# Power_Supply.net
KiCad netlist of a schematic drawn in Altium Designer
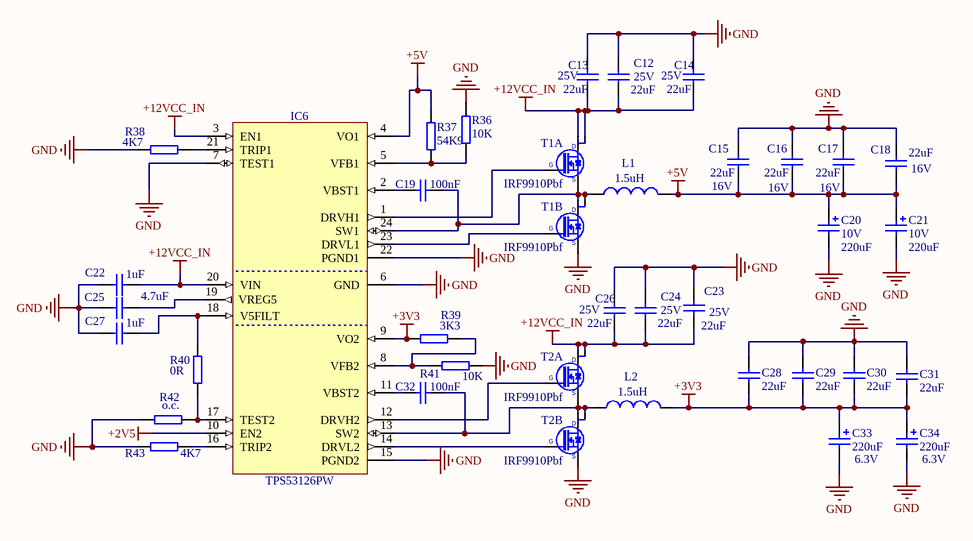
[diagram p0: Power_Supply.SchDoc]

(export (version "E")
  (design (tool "Eeschema 10.0.6"))
  (components
    (comp (ref "C12")
      (value "22uF")
      (footprint "CC3216-1206")
      (description "Capacitor")
      (fields
        (field (name "TOLERANCE") "±10%")
        (field (name "VOLTAGE") "25V")
        (field (name "Comment") "22uF 25V")
        (field (name "PUBLISHER") "Altium Limited")
      )
      (libsource (lib "wr_switch") (part "Cap"))
    )
    (comp (ref "C13")
      (value "22uF")
      (footprint "CC3216-1206")
      (description "Capacitor")
      (fields
        (field (name "TOLERANCE") "±10%")
        (field (name "VOLTAGE") "25V")
        (field (name "Comment") "22uF 25V")
        (field (name "PUBLISHER") "Altium Limited")
      )
      (libsource (lib "wr_switch") (part "Cap"))
    )
    (comp (ref "C14")
      (value "22uF")
      (footprint "CC3216-1206")
      (description "Capacitor")
      (fields
        (field (name "TOLERANCE") "±10%")
        (field (name "VOLTAGE") "25V")
        (field (name "Comment") "22uF 25V")
        (field (name "PUBLISHER") "Altium Limited")
      )
      (libsource (lib "wr_switch") (part "Cap"))
    )
    (comp (ref "C15")
      (value "22uF")
      (footprint "CC2012-0805")
      (description "Capacitor")
      (fields
        (field (name "TOLERANCE") "±10%")
        (field (name "VOLTAGE") "16V")
        (field (name "Comment") "22uF 16V")
        (field (name "PUBLISHER") "Altium Limited")
      )
      (libsource (lib "wr_switch") (part "Cap"))
    )
    (comp (ref "C16")
      (value "22uF")
      (footprint "CC2012-0805")
      (description "Capacitor")
      (fields
        (field (name "TOLERANCE") "±10%")
        (field (name "VOLTAGE") "16V")
        (field (name "Comment") "22uF 16V")
        (field (name "PUBLISHER") "Altium Limited")
      )
      (libsource (lib "wr_switch") (part "Cap"))
    )
    (comp (ref "C17")
      (value "22uF")
      (footprint "CC2012-0805")
      (description "Capacitor")
      (fields
        (field (name "TOLERANCE") "±10%")
        (field (name "VOLTAGE") "16V")
        (field (name "Comment") "22uF 16V")
        (field (name "PUBLISHER") "Altium Limited")
      )
      (libsource (lib "wr_switch") (part "Cap"))
    )
    (comp (ref "C18")
      (value "22uF")
      (footprint "CC2012-0805")
      (description "Capacitor")
      (fields
        (field (name "TOLERANCE") "±10%")
        (field (name "VOLTAGE") "16V")
        (field (name "Comment") "22uF 16V")
        (field (name "PUBLISHER") "Altium Limited")
      )
      (libsource (lib "wr_switch") (part "Cap"))
    )
    (comp (ref "C19")
      (value "100nF")
      (footprint "CC1608-0603")
      (description "Capacitor")
      (fields
        (field (name "TOLERANCE") "±10%")
        (field (name "VOLTAGE") "16V")
        (field (name "PUBLISHER") "Altium Limited")
      )
      (libsource (lib "wr_switch") (part "Cap"))
    )
    (comp (ref "C20")
      (value "220uF")
      (footprint "D")
      (description "Polarized Capacitor Tantalum")
      (fields
        (field (name "TOLERANCE") "±20%")
        (field (name "VOLTAGE") "10V")
        (field (name "Comment") "220uF 10V")
        (field (name "PUBLISHER") "Altium Limited")
      )
      (libsource (lib "wr_switch") (part "Cap Pol1"))
    )
    (comp (ref "C21")
      (value "220uF")
      (footprint "D")
      (description "Polarized Capacitor Tantalum")
      (fields
        (field (name "TOLERANCE") "±20%")
        (field (name "VOLTAGE") "10V")
        (field (name "Comment") "220uF 10V")
        (field (name "PUBLISHER") "Altium Limited")
      )
      (libsource (lib "wr_switch") (part "Cap Pol1"))
    )
    (comp (ref "C22")
      (value "1uF")
      (footprint "CC1608-0603")
      (description "Capacitor")
      (fields
        (field (name "TOLERANCE") "±10%")
        (field (name "VOLTAGE") "25V")
        (field (name "PUBLISHER") "Altium Limited")
      )
      (libsource (lib "wr_switch") (part "Cap"))
    )
    (comp (ref "C23")
      (value "22uF")
      (footprint "CC3216-1206")
      (description "Capacitor")
      (fields
        (field (name "TOLERANCE") "±10%")
        (field (name "VOLTAGE") "25V")
        (field (name "Comment") "22uF 25V")
        (field (name "PUBLISHER") "Altium Limited")
      )
      (libsource (lib "wr_switch") (part "Cap"))
    )
    (comp (ref "C24")
      (value "22uF")
      (footprint "CC3216-1206")
      (description "Capacitor")
      (fields
        (field (name "TOLERANCE") "±10%")
        (field (name "VOLTAGE") "25V")
        (field (name "Comment") "22uF 25V")
        (field (name "PUBLISHER") "Altium Limited")
      )
      (libsource (lib "wr_switch") (part "Cap"))
    )
    (comp (ref "C25")
      (value "4.7uF")
      (footprint "CC1608-0603")
      (description "Capacitor")
      (fields
        (field (name "TOLERANCE") "±10%")
        (field (name "VOLTAGE") "10V")
        (field (name "PUBLISHER") "Altium Limited")
      )
      (libsource (lib "wr_switch") (part "Cap"))
    )
    (comp (ref "C26")
      (value "22uF")
      (footprint "CC3216-1206")
      (description "Capacitor")
      (fields
        (field (name "TOLERANCE") "±10%")
        (field (name "VOLTAGE") "25V")
        (field (name "Comment") "22uF 25V")
        (field (name "PUBLISHER") "Altium Limited")
      )
      (libsource (lib "wr_switch") (part "Cap"))
    )
    (comp (ref "C27")
      (value "1uF")
      (footprint "CC1608-0603")
      (description "Capacitor")
      (fields
        (field (name "TOLERANCE") "±10%")
        (field (name "VOLTAGE") "25V")
        (field (name "PUBLISHER") "Altium Limited")
      )
      (libsource (lib "wr_switch") (part "Cap"))
    )
    (comp (ref "C28")
      (value "22uF")
      (footprint "CC2012-0805")
      (description "Capacitor")
      (fields
        (field (name "TOLERANCE") "±20%")
        (field (name "VOLTAGE") "6.3V")
        (field (name "PUBLISHER") "Altium Limited")
      )
      (libsource (lib "wr_switch") (part "Cap"))
    )
    (comp (ref "C29")
      (value "22uF")
      (footprint "CC2012-0805")
      (description "Capacitor")
      (fields
        (field (name "TOLERANCE") "±20%")
        (field (name "VOLTAGE") "6.3V")
        (field (name "PUBLISHER") "Altium Limited")
      )
      (libsource (lib "wr_switch") (part "Cap"))
    )
    (comp (ref "C30")
      (value "22uF")
      (footprint "CC2012-0805")
      (description "Capacitor")
      (fields
        (field (name "TOLERANCE") "±20%")
        (field (name "VOLTAGE") "6.3V")
        (field (name "PUBLISHER") "Altium Limited")
      )
      (libsource (lib "wr_switch") (part "Cap"))
    )
    (comp (ref "C31")
      (value "22uF")
      (footprint "CC2012-0805")
      (description "Capacitor")
      (fields
        (field (name "TOLERANCE") "±20%")
        (field (name "VOLTAGE") "6.3V")
        (field (name "PUBLISHER") "Altium Limited")
      )
      (libsource (lib "wr_switch") (part "Cap"))
    )
    (comp (ref "C32")
      (value "100nF")
      (footprint "CC1608-0603")
      (description "Capacitor")
      (fields
        (field (name "TOLERANCE") "±10%")
        (field (name "VOLTAGE") "16V")
        (field (name "PUBLISHER") "Altium Limited")
      )
      (libsource (lib "wr_switch") (part "Cap"))
    )
    (comp (ref "C33")
      (value "220uF")
      (footprint "D")
      (description "Polarized Capacitor Tantalum")
      (fields
        (field (name "TOLERANCE") "±20%")
        (field (name "VOLTAGE") "6.3V")
        (field (name "PUBLISHER") "Altium Limited")
      )
      (libsource (lib "wr_switch") (part "Cap Pol1"))
    )
    (comp (ref "C34")
      (value "220uF")
      (footprint "D")
      (description "Polarized Capacitor Tantalum")
      (fields
        (field (name "TOLERANCE") "±20%")
        (field (name "VOLTAGE") "6.3V")
        (field (name "PUBLISHER") "Altium Limited")
      )
      (libsource (lib "wr_switch") (part "Cap Pol1"))
    )
    (comp (ref "IC6")
      (value "TPS53126PW")
      (footprint "SOP65P640X120-24N")
      (description "Dual Synchronous Step-Down Controller For Low Voltage Power Rails")
      (fields (field (name "MANUFACTURER") "TEXAS INSTRUMENTS") (field (name "AUTHOR") "CERN DEM JLC"))
      (libsource (lib "wr_switch") (part "TPS53126PW"))
    )
    (comp (ref "L1")
      (value "1.5uH")
      (footprint "IHLP2525")
      (description "Low Profile, High Current Inductor")
      (fields
        (field (name "MANUFACTURER") "Vishay/Dale")
        (field (name "Comment") "IHLP2525CZER1R5M01")
        (field (name "PUBLISHER") "Altium Limited")
      )
      (libsource (lib "Miscellaneous Devices") (part "Inductor"))
    )
    (comp (ref "L2")
      (value "1.5uH")
      (footprint "IHLP2525")
      (description "Low Profile, High Current Inductor")
      (fields
        (field (name "MANUFACTURER") "Vishay/Dale")
        (field (name "Comment") "IHLP2525CZER1R5M01")
        (field (name "PUBLISHER") "Altium Limited")
      )
      (libsource (lib "Miscellaneous Devices") (part "Inductor"))
    )
    (comp (ref "R36")
      (value "10K")
      (footprint "0603")
      (description "SMD Resistor")
      (fields (field (name "TOLERANCE") "±1%"))
      (libsource (lib "wr_switch") (part "RES_SMD"))
    )
    (comp (ref "R37")
      (value "54K9")
      (footprint "0603")
      (description "SMD Resistor")
      (fields (field (name "TOLERANCE") "±1%"))
      (libsource (lib "wr_switch") (part "RES_SMD"))
    )
    (comp (ref "R38")
      (value "4K7")
      (footprint "0603")
      (description "SMD Resistor")
      (fields (field (name "TOLERANCE") "±1%"))
      (libsource (lib "wr_switch") (part "RES_SMD"))
    )
    (comp (ref "R39")
      (value "3K3")
      (footprint "0603")
      (description "SMD Resistor")
      (fields (field (name "TOLERANCE") "±1%"))
      (libsource (lib "wr_switch") (part "RES_SMD"))
    )
    (comp (ref "R40")
      (value "0R")
      (footprint "0603")
      (description "SMD Resistor")
      (libsource (lib "wr_switch") (part "RES_SMD"))
    )
    (comp (ref "R41")
      (value "10K")
      (footprint "0603")
      (description "SMD Resistor")
      (fields (field (name "TOLERANCE") "±1%"))
      (libsource (lib "wr_switch") (part "RES_SMD"))
    )
    (comp (ref "R42")
      (value "o.c.")
      (footprint "0603")
      (description "SMD Resistor")
      (fields (field (name "TOLERANCE") "NA"))
      (libsource (lib "wr_switch") (part "RES_SMD"))
    )
    (comp (ref "R43")
      (value "4K7")
      (footprint "0603")
      (description "SMD Resistor")
      (fields (field (name "TOLERANCE") "±1%"))
      (libsource (lib "wr_switch") (part "RES_SMD"))
    )
    (comp (ref "T1")
      (value "IRF9910Pbf")
      (footprint "SOIC127P600X175-8N")
      (description "Dual SO-8 MOSFET For POL Cconverter")
      (fields (field (name "MANUFACTURER") "INTERNATIONAL RECTIFIER") (field (name "AUTHOR") "CERN DEM JLC"))
      (libsource (lib "ICs And Semiconductors") (part "IRF9910"))
    )
    (comp (ref "T2")
      (value "IRF9910Pbf")
      (footprint "SOIC127P600X175-8N")
      (description "Dual SO-8 MOSFET For POL Cconverter")
      (fields (field (name "MANUFACTURER") "INTERNATIONAL RECTIFIER") (field (name "AUTHOR") "CERN DEM JLC"))
      (libsource (lib "ICs And Semiconductors") (part "IRF9910"))
    )
  )
  (nets
    (net (code "1") (name "+2V5") (class "Default")
      (node (ref "IC6") (pin "10") (pinfunction "EN2_10") (pintype "input"))
    )
    (net (code "2") (name "+3V3") (class "Default")
      (node (ref "C28") (pin "2") (pinfunction "2_2") (pintype "passive"))
      (node (ref "C29") (pin "1") (pinfunction "1_1") (pintype "passive"))
      (node (ref "C30") (pin "1") (pinfunction "1_1") (pintype "passive"))
      (node (ref "C31") (pin "1") (pinfunction "1_1") (pintype "passive"))
      (node (ref "C33") (pin "1") (pinfunction "1_1") (pintype "passive"))
      (node (ref "C34") (pin "1") (pinfunction "1_1") (pintype "passive"))
      (node (ref "IC6") (pin "9") (pinfunction "VO2_9") (pintype "input"))
      (node (ref "L2") (pin "2") (pinfunction "2_2") (pintype "passive"))
      (node (ref "R39") (pin "1") (pinfunction "1_1") (pintype "passive"))
    )
    (net (code "3") (name "+5V") (class "Default")
      (node (ref "C15") (pin "1") (pinfunction "1_1") (pintype "passive"))
      (node (ref "C16") (pin "1") (pinfunction "1_1") (pintype "passive"))
      (node (ref "C17") (pin "1") (pinfunction "1_1") (pintype "passive"))
      (node (ref "C18") (pin "1") (pinfunction "1_1") (pintype "passive"))
      (node (ref "C20") (pin "1") (pinfunction "1_1") (pintype "passive"))
      (node (ref "C21") (pin "1") (pinfunction "1_1") (pintype "passive"))
      (node (ref "IC6") (pin "4") (pinfunction "VO1_4") (pintype "input"))
      (node (ref "L1") (pin "2") (pinfunction "2_2") (pintype "passive"))
      (node (ref "R37") (pin "2") (pinfunction "2_2") (pintype "passive"))
    )
    (net (code "4") (name "+12VCC_IN") (class "Default")
      (node (ref "C12") (pin "1") (pinfunction "1_1") (pintype "passive"))
      (node (ref "C13") (pin "1") (pinfunction "1_1") (pintype "passive"))
      (node (ref "C14") (pin "1") (pinfunction "1_1") (pintype "passive"))
      (node (ref "C22") (pin "2") (pinfunction "2_2") (pintype "passive"))
      (node (ref "C23") (pin "1") (pinfunction "1_1") (pintype "passive"))
      (node (ref "C24") (pin "1") (pinfunction "1_1") (pintype "passive"))
      (node (ref "C26") (pin "1") (pinfunction "1_1") (pintype "passive"))
      (node (ref "IC6") (pin "20") (pinfunction "VIN_20") (pintype "input"))
      (node (ref "IC6") (pin "3") (pinfunction "EN1_3") (pintype "input"))
      (node (ref "T1") (pin "5") (pinfunction "D_5") (pintype "passive"))
      (node (ref "T1") (pin "6") (pinfunction "D_6") (pintype "passive"))
      (node (ref "T2") (pin "5") (pinfunction "D_5") (pintype "passive"))
      (node (ref "T2") (pin "6") (pinfunction "D_6") (pintype "passive"))
    )
    (net (code "5") (name "GND") (class "Default")
      (node (ref "C12") (pin "2") (pinfunction "2_2") (pintype "passive"))
      (node (ref "C13") (pin "2") (pinfunction "2_2") (pintype "passive"))
      (node (ref "C14") (pin "2") (pinfunction "2_2") (pintype "passive"))
      (node (ref "C15") (pin "2") (pinfunction "2_2") (pintype "passive"))
      (node (ref "C16") (pin "2") (pinfunction "2_2") (pintype "passive"))
      (node (ref "C17") (pin "2") (pinfunction "2_2") (pintype "passive"))
      (node (ref "C18") (pin "2") (pinfunction "2_2") (pintype "passive"))
      (node (ref "C20") (pin "2") (pinfunction "2_2") (pintype "passive"))
      (node (ref "C21") (pin "2") (pinfunction "2_2") (pintype "passive"))
      (node (ref "C22") (pin "1") (pinfunction "1_1") (pintype "passive"))
      (node (ref "C23") (pin "2") (pinfunction "2_2") (pintype "passive"))
      (node (ref "C24") (pin "2") (pinfunction "2_2") (pintype "passive"))
      (node (ref "C25") (pin "2") (pinfunction "2_2") (pintype "passive"))
      (node (ref "C26") (pin "2") (pinfunction "2_2") (pintype "passive"))
      (node (ref "C27") (pin "1") (pinfunction "1_1") (pintype "passive"))
      (node (ref "C28") (pin "1") (pinfunction "1_1") (pintype "passive"))
      (node (ref "C29") (pin "2") (pinfunction "2_2") (pintype "passive"))
      (node (ref "C30") (pin "2") (pinfunction "2_2") (pintype "passive"))
      (node (ref "C31") (pin "2") (pinfunction "2_2") (pintype "passive"))
      (node (ref "C33") (pin "2") (pinfunction "2_2") (pintype "passive"))
      (node (ref "C34") (pin "2") (pinfunction "2_2") (pintype "passive"))
      (node (ref "IC6") (pin "15") (pinfunction "PGND2_15") (pintype "power_in"))
      (node (ref "IC6") (pin "22") (pinfunction "PGND1_22") (pintype "power_in"))
      (node (ref "IC6") (pin "6") (pinfunction "GND_6") (pintype "power_in"))
      (node (ref "IC6") (pin "7") (pinfunction "TEST1_7") (pintype "bidirectional"))
      (node (ref "R36") (pin "2") (pinfunction "2_2") (pintype "passive"))
      (node (ref "R38") (pin "2") (pinfunction "2_2") (pintype "passive"))
      (node (ref "R41") (pin "1") (pinfunction "1_1") (pintype "passive"))
      (node (ref "R42") (pin "2") (pinfunction "2_2") (pintype "passive"))
      (node (ref "R43") (pin "2") (pinfunction "2_2") (pintype "passive"))
      (node (ref "T1") (pin "1") (pinfunction "S_1") (pintype "passive"))
      (node (ref "T2") (pin "1") (pinfunction "S_1") (pintype "passive"))
    )
    (net (code "6") (name "Net-(IC6-DRVH1)") (class "Default")
      (node (ref "IC6") (pin "1") (pinfunction "DRVH1_1") (pintype "output"))
      (node (ref "T1") (pin "4") (pinfunction "G_4") (pintype "passive"))
    )
    (net (code "7") (name "Net-(IC6-DRVH2)") (class "Default")
      (node (ref "IC6") (pin "12") (pinfunction "DRVH2_12") (pintype "output"))
      (node (ref "T2") (pin "4") (pinfunction "G_4") (pintype "passive"))
    )
    (net (code "8") (name "Net-(IC6-DRVL1)") (class "Default")
      (node (ref "IC6") (pin "23") (pinfunction "DRVL1_23") (pintype "output"))
      (node (ref "T1") (pin "2") (pinfunction "G_2") (pintype "passive"))
    )
    (net (code "9") (name "Net-(IC6-DRVL2)") (class "Default")
      (node (ref "IC6") (pin "14") (pinfunction "DRVL2_14") (pintype "output"))
      (node (ref "T2") (pin "2") (pinfunction "G_2") (pintype "passive"))
    )
    (net (code "10") (name "Net-(IC6-SW1)") (class "Default")
      (node (ref "C19") (pin "1") (pinfunction "1_1") (pintype "passive"))
      (node (ref "IC6") (pin "24") (pinfunction "SW1_24") (pintype "bidirectional"))
      (node (ref "L1") (pin "1") (pinfunction "1_1") (pintype "passive"))
      (node (ref "T1") (pin "3") (pinfunction "S_3") (pintype "passive"))
      (node (ref "T1") (pin "7") (pinfunction "D_7") (pintype "passive"))
      (node (ref "T1") (pin "8") (pinfunction "D_8") (pintype "passive"))
    )
    (net (code "11") (name "Net-(IC6-SW2)") (class "Default")
      (node (ref "C32") (pin "1") (pinfunction "1_1") (pintype "passive"))
      (node (ref "IC6") (pin "13") (pinfunction "SW2_13") (pintype "bidirectional"))
      (node (ref "L2") (pin "1") (pinfunction "1_1") (pintype "passive"))
      (node (ref "T2") (pin "3") (pinfunction "S_3") (pintype "passive"))
      (node (ref "T2") (pin "7") (pinfunction "D_7") (pintype "passive"))
      (node (ref "T2") (pin "8") (pinfunction "D_8") (pintype "passive"))
    )
    (net (code "12") (name "Net-(IC6-TEST2)") (class "Default")
      (node (ref "IC6") (pin "17") (pinfunction "TEST2_17") (pintype "input"))
      (node (ref "R40") (pin "2") (pinfunction "2_2") (pintype "passive"))
      (node (ref "R42") (pin "1") (pinfunction "1_1") (pintype "passive"))
    )
    (net (code "13") (name "Net-(IC6-TRIP1)") (class "Default")
      (node (ref "IC6") (pin "21") (pinfunction "TRIP1_21") (pintype "input"))
      (node (ref "R38") (pin "1") (pinfunction "1_1") (pintype "passive"))
    )
    (net (code "14") (name "Net-(IC6-TRIP2)") (class "Default")
      (node (ref "IC6") (pin "16") (pinfunction "TRIP2_16") (pintype "input"))
      (node (ref "R43") (pin "1") (pinfunction "1_1") (pintype "passive"))
    )
    (net (code "15") (name "Net-(IC6-V5FILT)") (class "Default")
      (node (ref "C27") (pin "2") (pinfunction "2_2") (pintype "passive"))
      (node (ref "IC6") (pin "18") (pinfunction "V5FILT_18") (pintype "input"))
      (node (ref "R40") (pin "1") (pinfunction "1_1") (pintype "passive"))
    )
    (net (code "16") (name "Net-(IC6-VBST1)") (class "Default")
      (node (ref "C19") (pin "2") (pinfunction "2_2") (pintype "passive"))
      (node (ref "IC6") (pin "2") (pinfunction "VBST1_2") (pintype "input"))
    )
    (net (code "17") (name "Net-(IC6-VBST2)") (class "Default")
      (node (ref "C32") (pin "2") (pinfunction "2_2") (pintype "passive"))
      (node (ref "IC6") (pin "11") (pinfunction "VBST2_11") (pintype "input"))
    )
    (net (code "18") (name "Net-(IC6-VFB1)") (class "Default")
      (node (ref "IC6") (pin "5") (pinfunction "VFB1_5") (pintype "input"))
      (node (ref "R36") (pin "1") (pinfunction "1_1") (pintype "passive"))
      (node (ref "R37") (pin "1") (pinfunction "1_1") (pintype "passive"))
    )
    (net (code "19") (name "Net-(IC6-VFB2)") (class "Default")
      (node (ref "IC6") (pin "8") (pinfunction "VFB2_8") (pintype "input"))
      (node (ref "R39") (pin "2") (pinfunction "2_2") (pintype "passive"))
      (node (ref "R41") (pin "2") (pinfunction "2_2") (pintype "passive"))
    )
    (net (code "20") (name "Net-(IC6-VREG5)") (class "Default")
      (node (ref "C25") (pin "1") (pinfunction "1_1") (pintype "passive"))
      (node (ref "IC6") (pin "19") (pinfunction "VREG5_19") (pintype "output"))
    )
  )
)
